# WS2812B_LED_Breakout.net
KiCad netlist of a schematic drawn in EAGLE
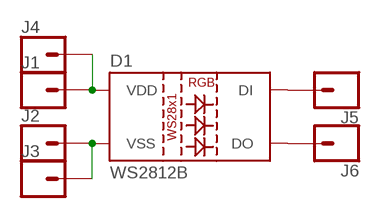
[diagram p0: schematic, sheet 1]

(export (version "E")
  (design (tool "Eeschema 10.0.6"))
  (components
    (comp (ref "D1")
      (value "WS2812B")
      (footprint "eagle-import:WS2812B")
      (libsource (lib "eagle-import") (part "WS2812B"))
    )
    (comp (ref "J1")
      (value "CONN_01PTH_LONGPAD")
      (footprint "eagle-import:1X01_LONGPAD")
      (libsource (lib "eagle-import") (part "CONN_01PTH_LONGPAD"))
    )
    (comp (ref "J2")
      (value "CONN_01PTH_LONGPAD")
      (footprint "eagle-import:1X01_LONGPAD")
      (libsource (lib "eagle-import") (part "CONN_01PTH_LONGPAD"))
    )
    (comp (ref "J3")
      (value "CONN_01PTH_LONGPAD")
      (footprint "eagle-import:1X01_LONGPAD")
      (libsource (lib "eagle-import") (part "CONN_01PTH_LONGPAD"))
    )
    (comp (ref "J4")
      (value "CONN_01PTH_LONGPAD")
      (footprint "eagle-import:1X01_LONGPAD")
      (libsource (lib "eagle-import") (part "CONN_01PTH_LONGPAD"))
    )
    (comp (ref "J5")
      (value "CONN_01PTH_LONGPAD")
      (footprint "eagle-import:1X01_LONGPAD")
      (libsource (lib "eagle-import") (part "CONN_01PTH_LONGPAD"))
    )
    (comp (ref "J6")
      (value "CONN_01PTH_LONGPAD")
      (footprint "eagle-import:1X01_LONGPAD")
      (libsource (lib "eagle-import") (part "CONN_01PTH_LONGPAD"))
    )
  )
  (nets
    (net (code "1") (name "Net-(D1-DI)") (class "Default")
      (node (ref "D1") (pin "4") (pinfunction "DI_4") (pintype "bidirectional"))
      (node (ref "J5") (pin "1") (pinfunction "1_1") (pintype "passive"))
    )
    (net (code "2") (name "Net-(D1-DO)") (class "Default")
      (node (ref "D1") (pin "2") (pinfunction "DO_2") (pintype "bidirectional"))
      (node (ref "J6") (pin "1") (pinfunction "1_1") (pintype "passive"))
    )
    (net (code "3") (name "Net-(D1-VDD)") (class "Default")
      (node (ref "D1") (pin "1") (pinfunction "VDD_1") (pintype "bidirectional"))
      (node (ref "J1") (pin "1") (pinfunction "1_1") (pintype "passive"))
      (node (ref "J4") (pin "1") (pinfunction "1_1") (pintype "passive"))
    )
    (net (code "4") (name "Net-(D1-VSS)") (class "Default")
      (node (ref "D1") (pin "3") (pinfunction "VSS_3") (pintype "bidirectional"))
      (node (ref "J2") (pin "1") (pinfunction "1_1") (pintype "passive"))
      (node (ref "J3") (pin "1") (pinfunction "1_1") (pintype "passive"))
    )
  )
)
